# MacroPad.net
KiCad netlist of a schematic drawn in EAGLE
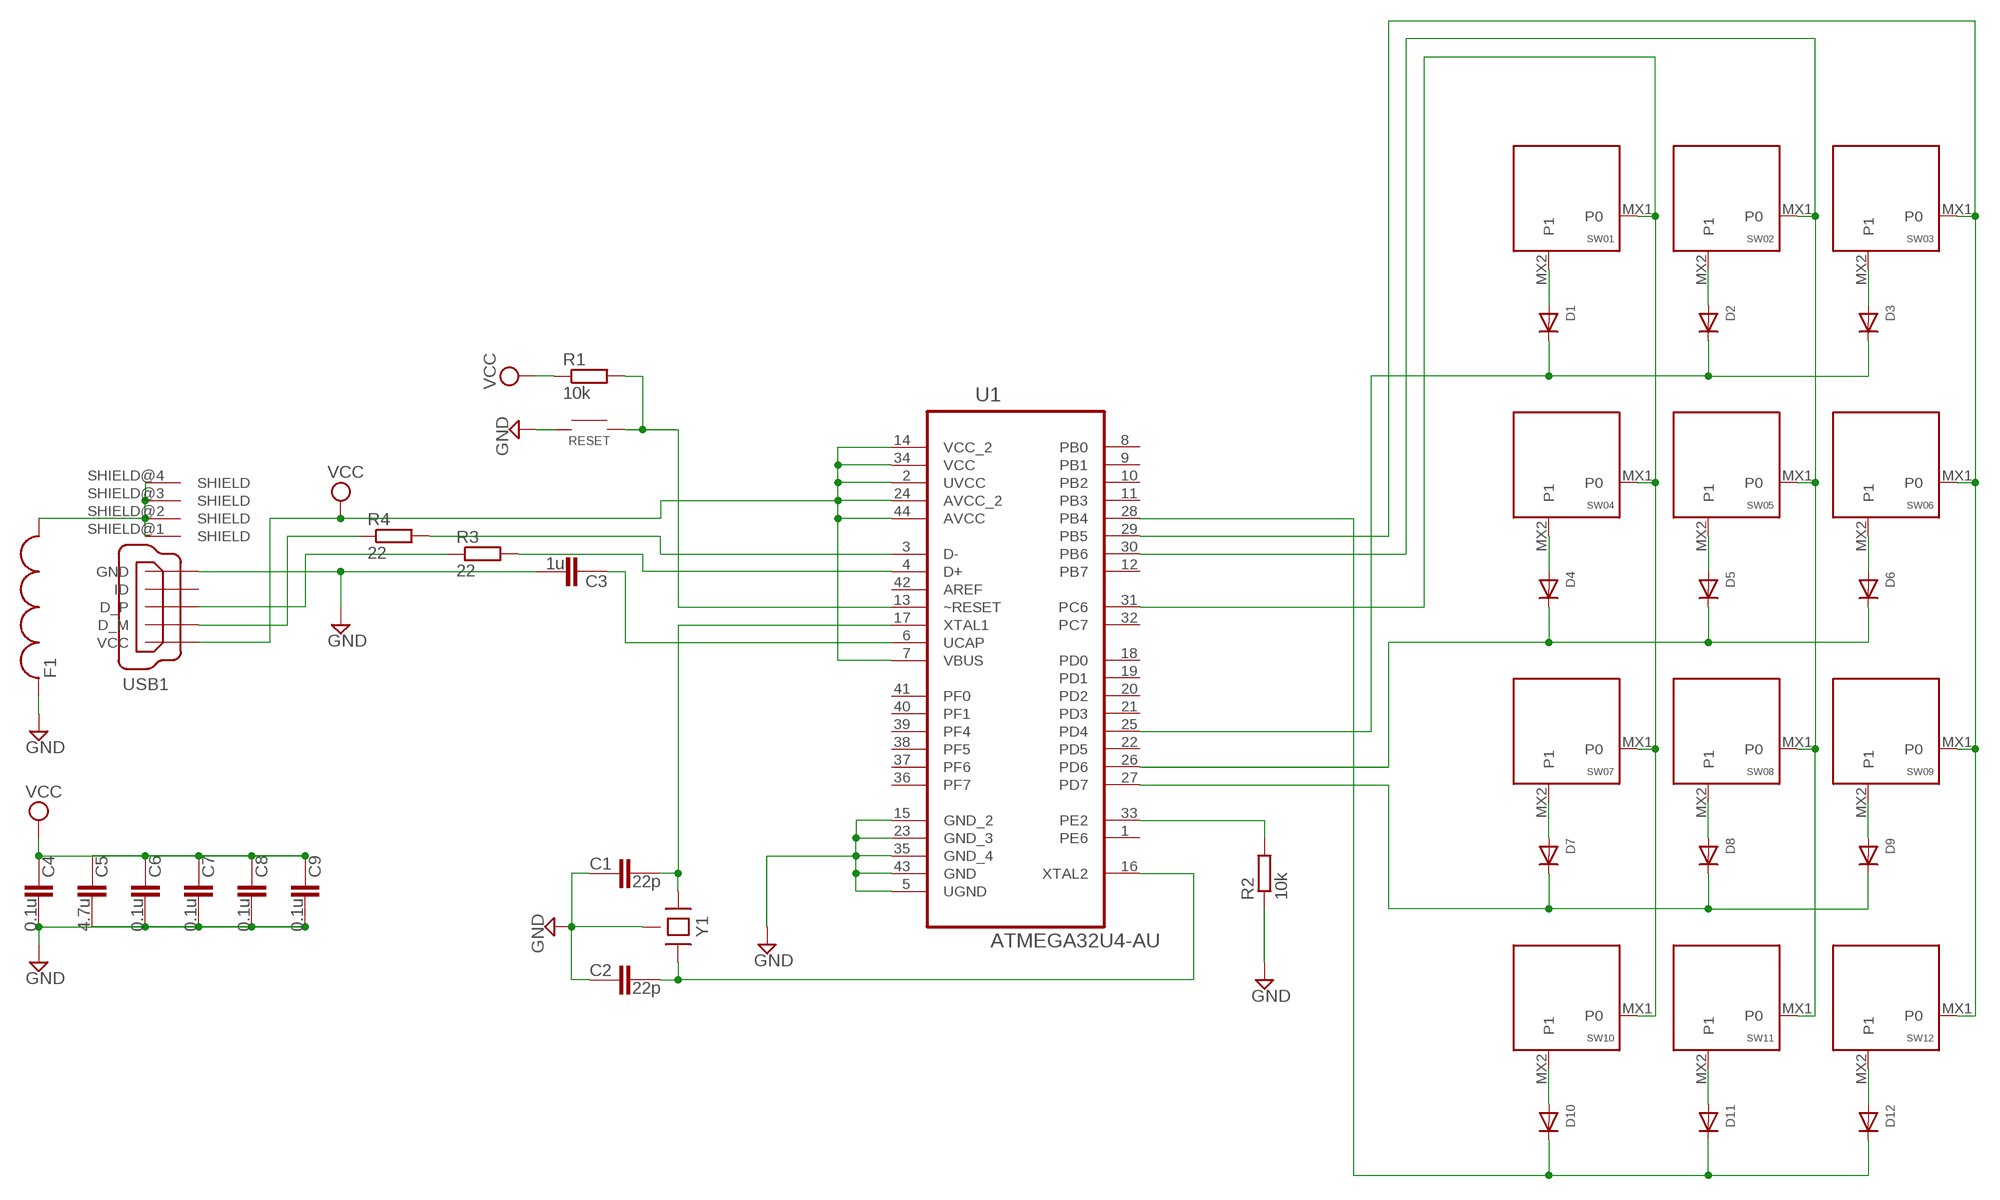
[diagram p0: schematic, sheet 1]

(export (version "E")
  (design (tool "Eeschema 10.0.6"))
  (components
    (comp (ref "C1")
      (value "22p")
      (footprint "eagle-import:C0603")
      (fields (field (name "MPN") "04025A220JAT2A"))
      (libsource (lib "eagle-import") (part "CAPACITOR-0603"))
    )
    (comp (ref "C2")
      (value "22p")
      (footprint "eagle-import:C0603")
      (fields (field (name "MPN") "04025A220JAT2A"))
      (libsource (lib "eagle-import") (part "CAPACITOR-0603"))
    )
    (comp (ref "C3")
      (value "1u")
      (footprint "eagle-import:C0603")
      (libsource (lib "eagle-import") (part "CAPACITOR-0603"))
    )
    (comp (ref "C4")
      (value "0.1u")
      (footprint "eagle-import:C0603")
      (libsource (lib "eagle-import") (part "CAPACITOR-0603"))
    )
    (comp (ref "C5")
      (value "4.7u")
      (footprint "eagle-import:C0603")
      (libsource (lib "eagle-import") (part "CAPACITOR-0603"))
    )
    (comp (ref "C6")
      (value "0.1u")
      (footprint "eagle-import:C0603")
      (libsource (lib "eagle-import") (part "CAPACITOR-0603"))
    )
    (comp (ref "C7")
      (value "0.1u")
      (footprint "eagle-import:C0603")
      (libsource (lib "eagle-import") (part "CAPACITOR-0603"))
    )
    (comp (ref "C8")
      (value "0.1u")
      (footprint "eagle-import:C0603")
      (libsource (lib "eagle-import") (part "CAPACITOR-0603"))
    )
    (comp (ref "C9")
      (value "0.1u")
      (footprint "eagle-import:C0603")
      (libsource (lib "eagle-import") (part "CAPACITOR-0603"))
    )
    (comp (ref "D1")
      (value "DIODEDO-1N4148")
      (footprint "eagle-import:DO-1N4148")
      (libsource (lib "eagle-import") (part "DIODEDO-1N4148"))
    )
    (comp (ref "D2")
      (value "DIODEDO-1N4148")
      (footprint "eagle-import:DO-1N4148")
      (libsource (lib "eagle-import") (part "DIODEDO-1N4148"))
    )
    (comp (ref "D3")
      (value "DIODEDO-1N4148")
      (footprint "eagle-import:DO-1N4148")
      (libsource (lib "eagle-import") (part "DIODEDO-1N4148"))
    )
    (comp (ref "D4")
      (value "DIODEDO-1N4148")
      (footprint "eagle-import:DO-1N4148")
      (libsource (lib "eagle-import") (part "DIODEDO-1N4148"))
    )
    (comp (ref "D5")
      (value "DIODEDO-1N4148")
      (footprint "eagle-import:DO-1N4148")
      (libsource (lib "eagle-import") (part "DIODEDO-1N4148"))
    )
    (comp (ref "D6")
      (value "DIODEDO-1N4148")
      (footprint "eagle-import:DO-1N4148")
      (libsource (lib "eagle-import") (part "DIODEDO-1N4148"))
    )
    (comp (ref "D7")
      (value "DIODEDO-1N4148")
      (footprint "eagle-import:DO-1N4148")
      (libsource (lib "eagle-import") (part "DIODEDO-1N4148"))
    )
    (comp (ref "D8")
      (value "DIODEDO-1N4148")
      (footprint "eagle-import:DO-1N4148")
      (libsource (lib "eagle-import") (part "DIODEDO-1N4148"))
    )
    (comp (ref "D9")
      (value "DIODEDO-1N4148")
      (footprint "eagle-import:DO-1N4148")
      (libsource (lib "eagle-import") (part "DIODEDO-1N4148"))
    )
    (comp (ref "D10")
      (value "DIODEDO-1N4148")
      (footprint "eagle-import:DO-1N4148")
      (libsource (lib "eagle-import") (part "DIODEDO-1N4148"))
    )
    (comp (ref "D11")
      (value "DIODEDO-1N4148")
      (footprint "eagle-import:DO-1N4148")
      (libsource (lib "eagle-import") (part "DIODEDO-1N4148"))
    )
    (comp (ref "D12")
      (value "DIODEDO-1N4148")
      (footprint "eagle-import:DO-1N4148")
      (libsource (lib "eagle-import") (part "DIODEDO-1N4148"))
    )
    (comp (ref "F1")
      (value "FERRITE-0805")
      (footprint "eagle-import:F0805")
      (libsource (lib "eagle-import") (part "FERRITE-0805"))
    )
    (comp (ref "R1")
      (value "10k")
      (footprint "eagle-import:R0603")
      (libsource (lib "eagle-import") (part "RESISTOR-0603"))
    )
    (comp (ref "R2")
      (value "10k")
      (footprint "eagle-import:R0603")
      (libsource (lib "eagle-import") (part "RESISTOR-0603"))
    )
    (comp (ref "R3")
      (value "22")
      (footprint "eagle-import:R0603")
      (libsource (lib "eagle-import") (part "RESISTOR-0603"))
    )
    (comp (ref "R4")
      (value "22")
      (footprint "eagle-import:R0603")
      (libsource (lib "eagle-import") (part "RESISTOR-0603"))
    )
    (comp (ref "RESET")
      (value "SWITCH-SMD-EVQP-P2602W")
      (footprint "eagle-import:SWITCH-SMD-EVQP-P2602W")
      (libsource (lib "eagle-import") (part "SWITCH-SMD-EVQP-P2602W"))
    )
    (comp (ref "SW01")
      (value "KEYSWITCH-PLAIN-MX-1U")
      (footprint "eagle-import:MX-1U")
      (libsource (lib "eagle-import") (part "KEYSWITCH-PLAIN-MX-1U"))
    )
    (comp (ref "SW02")
      (value "KEYSWITCH-PLAIN-MX-1U")
      (footprint "eagle-import:MX-1U")
      (libsource (lib "eagle-import") (part "KEYSWITCH-PLAIN-MX-1U"))
    )
    (comp (ref "SW03")
      (value "KEYSWITCH-PLAIN-MX-1U")
      (footprint "eagle-import:MX-1U")
      (libsource (lib "eagle-import") (part "KEYSWITCH-PLAIN-MX-1U"))
    )
    (comp (ref "SW04")
      (value "KEYSWITCH-PLAIN-MX-1U")
      (footprint "eagle-import:MX-1U")
      (libsource (lib "eagle-import") (part "KEYSWITCH-PLAIN-MX-1U"))
    )
    (comp (ref "SW05")
      (value "KEYSWITCH-PLAIN-MX-1U")
      (footprint "eagle-import:MX-1U")
      (libsource (lib "eagle-import") (part "KEYSWITCH-PLAIN-MX-1U"))
    )
    (comp (ref "SW06")
      (value "KEYSWITCH-PLAIN-MX-1U")
      (footprint "eagle-import:MX-1U")
      (libsource (lib "eagle-import") (part "KEYSWITCH-PLAIN-MX-1U"))
    )
    (comp (ref "SW07")
      (value "KEYSWITCH-PLAIN-MX-1U")
      (footprint "eagle-import:MX-1U")
      (libsource (lib "eagle-import") (part "KEYSWITCH-PLAIN-MX-1U"))
    )
    (comp (ref "SW08")
      (value "KEYSWITCH-PLAIN-MX-1U")
      (footprint "eagle-import:MX-1U")
      (libsource (lib "eagle-import") (part "KEYSWITCH-PLAIN-MX-1U"))
    )
    (comp (ref "SW09")
      (value "KEYSWITCH-PLAIN-MX-1U")
      (footprint "eagle-import:MX-1U")
      (libsource (lib "eagle-import") (part "KEYSWITCH-PLAIN-MX-1U"))
    )
    (comp (ref "SW10")
      (value "KEYSWITCH-PLAIN-MX-1U")
      (footprint "eagle-import:MX-1U")
      (libsource (lib "eagle-import") (part "KEYSWITCH-PLAIN-MX-1U"))
    )
    (comp (ref "SW11")
      (value "KEYSWITCH-PLAIN-MX-1U")
      (footprint "eagle-import:MX-1U")
      (libsource (lib "eagle-import") (part "KEYSWITCH-PLAIN-MX-1U"))
    )
    (comp (ref "SW12")
      (value "KEYSWITCH-PLAIN-MX-1U")
      (footprint "eagle-import:MX-1U")
      (libsource (lib "eagle-import") (part "KEYSWITCH-PLAIN-MX-1U"))
    )
    (comp (ref "U1")
      (value "ATMEGA32U4-AU")
      (footprint "eagle-import:QFP80P1200X1200X120-44N")
      (fields (field (name "MF") "Microchip"))
      (libsource (lib "eagle-import") (part "ATMEGA32U4-AU"))
    )
    (comp (ref "USB1")
      (value "USB_CONN-MINI-FEMALE")
      (footprint "eagle-import:UX60-MB-5S8")
      (libsource (lib "eagle-import") (part "USB_CONN-MINI-FEMALE"))
    )
    (comp (ref "Y1")
      (value "CRYSTAL-4PIN-3.2X5")
      (footprint "eagle-import:CRYSTAL-3.2X5")
      (libsource (lib "eagle-import") (part "CRYSTAL-4PIN-3.2X5"))
    )
  )
  (nets
    (net (code "1") (name "GND") (class "Default")
      (node (ref "C1") (pin "1") (pinfunction "1_1") (pintype "passive"))
      (node (ref "C2") (pin "1") (pinfunction "1_1") (pintype "passive"))
      (node (ref "C3") (pin "2") (pinfunction "2_2") (pintype "passive"))
      (node (ref "C4") (pin "2") (pinfunction "2_2") (pintype "passive"))
      (node (ref "C5") (pin "2") (pinfunction "2_2") (pintype "passive"))
      (node (ref "C6") (pin "2") (pinfunction "2_2") (pintype "passive"))
      (node (ref "C7") (pin "2") (pinfunction "2_2") (pintype "passive"))
      (node (ref "C8") (pin "2") (pinfunction "2_2") (pintype "passive"))
      (node (ref "C9") (pin "2") (pinfunction "2_2") (pintype "passive"))
      (node (ref "F1") (pin "1") (pinfunction "P$1_1") (pintype "bidirectional"))
      (node (ref "R2") (pin "1") (pinfunction "1_1") (pintype "passive"))
      (node (ref "RESET") (pin "1A") (pinfunction "1_1A") (pintype "passive"))
      (node (ref "RESET") (pin "1B") (pinfunction "1_1B") (pintype "passive"))
      (node (ref "U1") (pin "15") (pinfunction "GND_2_15") (pintype "passive"))
      (node (ref "U1") (pin "23") (pinfunction "GND_3_23") (pintype "passive"))
      (node (ref "U1") (pin "35") (pinfunction "GND_4_35") (pintype "passive"))
      (node (ref "U1") (pin "43") (pinfunction "GND_43") (pintype "passive"))
      (node (ref "U1") (pin "5") (pinfunction "UGND_5") (pintype "passive"))
      (node (ref "USB1") (pin "GND") (pinfunction "GND_GND") (pintype "input"))
      (node (ref "Y1") (pin "2") (pinfunction "GND_2") (pintype "bidirectional"))
      (node (ref "Y1") (pin "4") (pinfunction "GND_4") (pintype "bidirectional"))
    )
    (net (code "2") (name "Net-(F1-P$2)") (class "Default")
      (node (ref "F1") (pin "2") (pinfunction "P$2_2") (pintype "bidirectional"))
      (node (ref "USB1") (pin "SHIELD@1") (pinfunction "SHIELD_SHIELD@1") (pintype "bidirectional"))
      (node (ref "USB1") (pin "SHIELD@2") (pinfunction "SHIELD_SHIELD@2") (pintype "bidirectional"))
      (node (ref "USB1") (pin "SHIELD@3") (pinfunction "SHIELD_SHIELD@3") (pintype "bidirectional"))
      (node (ref "USB1") (pin "SHIELD@4") (pinfunction "SHIELD_SHIELD@4") (pintype "bidirectional"))
    )
    (net (code "3") (name "Net-(SW01-P0)") (class "Default")
      (node (ref "SW01") (pin "MX1") (pinfunction "P0_MX1") (pintype "bidirectional"))
      (node (ref "SW04") (pin "MX1") (pinfunction "P0_MX1") (pintype "bidirectional"))
      (node (ref "SW07") (pin "MX1") (pinfunction "P0_MX1") (pintype "bidirectional"))
      (node (ref "SW10") (pin "MX1") (pinfunction "P0_MX1") (pintype "bidirectional"))
      (node (ref "U1") (pin "31") (pinfunction "PC6_31") (pintype "bidirectional"))
    )
    (net (code "4") (name "Net-(SW01-P1)") (class "Default")
      (node (ref "D1") (pin "A") (pinfunction "A_A") (pintype "passive"))
      (node (ref "SW01") (pin "MX2") (pinfunction "P1_MX2") (pintype "bidirectional"))
    )
    (net (code "5") (name "Net-(SW02-P0)") (class "Default")
      (node (ref "SW02") (pin "MX1") (pinfunction "P0_MX1") (pintype "bidirectional"))
      (node (ref "SW05") (pin "MX1") (pinfunction "P0_MX1") (pintype "bidirectional"))
      (node (ref "SW08") (pin "MX1") (pinfunction "P0_MX1") (pintype "bidirectional"))
      (node (ref "SW11") (pin "MX1") (pinfunction "P0_MX1") (pintype "bidirectional"))
      (node (ref "U1") (pin "30") (pinfunction "PB6_30") (pintype "bidirectional"))
    )
    (net (code "6") (name "Net-(SW02-P1)") (class "Default")
      (node (ref "D2") (pin "A") (pinfunction "A_A") (pintype "passive"))
      (node (ref "SW02") (pin "MX2") (pinfunction "P1_MX2") (pintype "bidirectional"))
    )
    (net (code "7") (name "Net-(SW03-P0)") (class "Default")
      (node (ref "SW03") (pin "MX1") (pinfunction "P0_MX1") (pintype "bidirectional"))
      (node (ref "SW06") (pin "MX1") (pinfunction "P0_MX1") (pintype "bidirectional"))
      (node (ref "SW09") (pin "MX1") (pinfunction "P0_MX1") (pintype "bidirectional"))
      (node (ref "SW12") (pin "MX1") (pinfunction "P0_MX1") (pintype "bidirectional"))
      (node (ref "U1") (pin "29") (pinfunction "PB5_29") (pintype "bidirectional"))
    )
    (net (code "8") (name "Net-(SW03-P1)") (class "Default")
      (node (ref "D3") (pin "A") (pinfunction "A_A") (pintype "passive"))
      (node (ref "SW03") (pin "MX2") (pinfunction "P1_MX2") (pintype "bidirectional"))
    )
    (net (code "9") (name "Net-(SW04-P1)") (class "Default")
      (node (ref "D4") (pin "A") (pinfunction "A_A") (pintype "passive"))
      (node (ref "SW04") (pin "MX2") (pinfunction "P1_MX2") (pintype "bidirectional"))
    )
    (net (code "10") (name "Net-(SW05-P1)") (class "Default")
      (node (ref "D5") (pin "A") (pinfunction "A_A") (pintype "passive"))
      (node (ref "SW05") (pin "MX2") (pinfunction "P1_MX2") (pintype "bidirectional"))
    )
    (net (code "11") (name "Net-(SW06-P1)") (class "Default")
      (node (ref "D6") (pin "A") (pinfunction "A_A") (pintype "passive"))
      (node (ref "SW06") (pin "MX2") (pinfunction "P1_MX2") (pintype "bidirectional"))
    )
    (net (code "12") (name "Net-(SW07-P1)") (class "Default")
      (node (ref "D7") (pin "A") (pinfunction "A_A") (pintype "passive"))
      (node (ref "SW07") (pin "MX2") (pinfunction "P1_MX2") (pintype "bidirectional"))
    )
    (net (code "13") (name "Net-(SW08-P1)") (class "Default")
      (node (ref "D8") (pin "A") (pinfunction "A_A") (pintype "passive"))
      (node (ref "SW08") (pin "MX2") (pinfunction "P1_MX2") (pintype "bidirectional"))
    )
    (net (code "14") (name "Net-(SW09-P1)") (class "Default")
      (node (ref "D9") (pin "A") (pinfunction "A_A") (pintype "passive"))
      (node (ref "SW09") (pin "MX2") (pinfunction "P1_MX2") (pintype "bidirectional"))
    )
    (net (code "15") (name "Net-(SW10-P1)") (class "Default")
      (node (ref "D10") (pin "A") (pinfunction "A_A") (pintype "passive"))
      (node (ref "SW10") (pin "MX2") (pinfunction "P1_MX2") (pintype "bidirectional"))
    )
    (net (code "16") (name "Net-(SW11-P1)") (class "Default")
      (node (ref "D11") (pin "A") (pinfunction "A_A") (pintype "passive"))
      (node (ref "SW11") (pin "MX2") (pinfunction "P1_MX2") (pintype "bidirectional"))
    )
    (net (code "17") (name "Net-(SW12-P1)") (class "Default")
      (node (ref "D12") (pin "A") (pinfunction "A_A") (pintype "passive"))
      (node (ref "SW12") (pin "MX2") (pinfunction "P1_MX2") (pintype "bidirectional"))
    )
    (net (code "18") (name "Net-(U1-D+)") (class "Default")
      (node (ref "R3") (pin "2") (pinfunction "2_2") (pintype "passive"))
      (node (ref "U1") (pin "4") (pinfunction "D+_4") (pintype "passive"))
    )
    (net (code "19") (name "Net-(U1-D-)") (class "Default")
      (node (ref "R4") (pin "2") (pinfunction "2_2") (pintype "passive"))
      (node (ref "U1") (pin "3") (pinfunction "D-_3") (pintype "passive"))
    )
    (net (code "20") (name "Net-(U1-PB4)") (class "Default")
      (node (ref "D10") (pin "C") (pinfunction "C_C") (pintype "passive"))
      (node (ref "D11") (pin "C") (pinfunction "C_C") (pintype "passive"))
      (node (ref "D12") (pin "C") (pinfunction "C_C") (pintype "passive"))
      (node (ref "U1") (pin "28") (pinfunction "PB4_28") (pintype "bidirectional"))
    )
    (net (code "21") (name "Net-(U1-PD4)") (class "Default")
      (node (ref "D1") (pin "C") (pinfunction "C_C") (pintype "passive"))
      (node (ref "D2") (pin "C") (pinfunction "C_C") (pintype "passive"))
      (node (ref "D3") (pin "C") (pinfunction "C_C") (pintype "passive"))
      (node (ref "U1") (pin "25") (pinfunction "PD4_25") (pintype "bidirectional"))
    )
    (net (code "22") (name "Net-(U1-PD6)") (class "Default")
      (node (ref "D4") (pin "C") (pinfunction "C_C") (pintype "passive"))
      (node (ref "D5") (pin "C") (pinfunction "C_C") (pintype "passive"))
      (node (ref "D6") (pin "C") (pinfunction "C_C") (pintype "passive"))
      (node (ref "U1") (pin "26") (pinfunction "PD6_26") (pintype "bidirectional"))
    )
    (net (code "23") (name "Net-(U1-PD7)") (class "Default")
      (node (ref "D7") (pin "C") (pinfunction "C_C") (pintype "passive"))
      (node (ref "D8") (pin "C") (pinfunction "C_C") (pintype "passive"))
      (node (ref "D9") (pin "C") (pinfunction "C_C") (pintype "passive"))
      (node (ref "U1") (pin "27") (pinfunction "PD7_27") (pintype "bidirectional"))
    )
    (net (code "24") (name "Net-(U1-PE2)") (class "Default")
      (node (ref "R2") (pin "2") (pinfunction "2_2") (pintype "passive"))
      (node (ref "U1") (pin "33") (pinfunction "PE2_33") (pintype "bidirectional"))
    )
    (net (code "25") (name "Net-(U1-UCAP)") (class "Default")
      (node (ref "C3") (pin "1") (pinfunction "1_1") (pintype "passive"))
      (node (ref "U1") (pin "6") (pinfunction "UCAP_6") (pintype "power_in"))
    )
    (net (code "26") (name "Net-(U1-XTAL1)") (class "Default")
      (node (ref "C1") (pin "2") (pinfunction "2_2") (pintype "passive"))
      (node (ref "U1") (pin "17") (pinfunction "XTAL1_17") (pintype "input"))
      (node (ref "Y1") (pin "1") (pinfunction "1_1") (pintype "passive"))
    )
    (net (code "27") (name "Net-(U1-XTAL2)") (class "Default")
      (node (ref "C2") (pin "2") (pinfunction "2_2") (pintype "passive"))
      (node (ref "U1") (pin "16") (pinfunction "XTAL2_16") (pintype "output"))
      (node (ref "Y1") (pin "3") (pinfunction "2_3") (pintype "passive"))
    )
    (net (code "28") (name "Net-(U1-~{RESET})") (class "Default")
      (node (ref "R1") (pin "2") (pinfunction "2_2") (pintype "passive"))
      (node (ref "RESET") (pin "2A") (pinfunction "2_2A") (pintype "passive"))
      (node (ref "RESET") (pin "2B") (pinfunction "2_2B") (pintype "passive"))
      (node (ref "U1") (pin "13") (pinfunction "~{RESET}_13") (pintype "input"))
    )
    (net (code "29") (name "Net-(USB1-D_M)") (class "Default")
      (node (ref "R4") (pin "1") (pinfunction "1_1") (pintype "passive"))
      (node (ref "USB1") (pin "D-") (pinfunction "D_M_D-") (pintype "input"))
    )
    (net (code "30") (name "Net-(USB1-D_P)") (class "Default")
      (node (ref "R3") (pin "1") (pinfunction "1_1") (pintype "passive"))
      (node (ref "USB1") (pin "D+") (pinfunction "D_P_D+") (pintype "input"))
    )
    (net (code "31") (name "VCC") (class "Default")
      (node (ref "C4") (pin "1") (pinfunction "1_1") (pintype "passive"))
      (node (ref "C5") (pin "1") (pinfunction "1_1") (pintype "passive"))
      (node (ref "C6") (pin "1") (pinfunction "1_1") (pintype "passive"))
      (node (ref "C7") (pin "1") (pinfunction "1_1") (pintype "passive"))
      (node (ref "C8") (pin "1") (pinfunction "1_1") (pintype "passive"))
      (node (ref "C9") (pin "1") (pinfunction "1_1") (pintype "passive"))
      (node (ref "R1") (pin "1") (pinfunction "1_1") (pintype "passive"))
      (node (ref "U1") (pin "14") (pinfunction "VCC_2_14") (pintype "power_in"))
      (node (ref "U1") (pin "2") (pinfunction "UVCC_2") (pintype "power_in"))
      (node (ref "U1") (pin "24") (pinfunction "AVCC_2_24") (pintype "power_in"))
      (node (ref "U1") (pin "34") (pinfunction "VCC_34") (pintype "power_in"))
      (node (ref "U1") (pin "44") (pinfunction "AVCC_44") (pintype "power_in"))
      (node (ref "U1") (pin "7") (pinfunction "VBUS_7") (pintype "input"))
      (node (ref "USB1") (pin "VCC") (pinfunction "VCC_VCC") (pintype "input"))
    )
    (net (code "32") (name "unconnected-(U1-AREF-Pad42)") (class "Default")
      (node (ref "U1") (pin "42") (pinfunction "AREF_42") (pintype "input"))
    )
    (net (code "33") (name "unconnected-(U1-PB0-Pad8)") (class "Default")
      (node (ref "U1") (pin "8") (pinfunction "PB0_8") (pintype "bidirectional"))
    )
    (net (code "34") (name "unconnected-(U1-PB1-Pad9)") (class "Default")
      (node (ref "U1") (pin "9") (pinfunction "PB1_9") (pintype "bidirectional"))
    )
    (net (code "35") (name "unconnected-(U1-PB2-Pad10)") (class "Default")
      (node (ref "U1") (pin "10") (pinfunction "PB2_10") (pintype "bidirectional"))
    )
    (net (code "36") (name "unconnected-(U1-PB3-Pad11)") (class "Default")
      (node (ref "U1") (pin "11") (pinfunction "PB3_11") (pintype "bidirectional"))
    )
    (net (code "37") (name "unconnected-(U1-PB7-Pad12)") (class "Default")
      (node (ref "U1") (pin "12") (pinfunction "PB7_12") (pintype "bidirectional"))
    )
    (net (code "38") (name "unconnected-(U1-PC7-Pad32)") (class "Default")
      (node (ref "U1") (pin "32") (pinfunction "PC7_32") (pintype "bidirectional"))
    )
    (net (code "39") (name "unconnected-(U1-PD0-Pad18)") (class "Default")
      (node (ref "U1") (pin "18") (pinfunction "PD0_18") (pintype "bidirectional"))
    )
    (net (code "40") (name "unconnected-(U1-PD1-Pad19)") (class "Default")
      (node (ref "U1") (pin "19") (pinfunction "PD1_19") (pintype "bidirectional"))
    )
    (net (code "41") (name "unconnected-(U1-PD2-Pad20)") (class "Default")
      (node (ref "U1") (pin "20") (pinfunction "PD2_20") (pintype "bidirectional"))
    )
    (net (code "42") (name "unconnected-(U1-PD3-Pad21)") (class "Default")
      (node (ref "U1") (pin "21") (pinfunction "PD3_21") (pintype "bidirectional"))
    )
    (net (code "43") (name "unconnected-(U1-PD5-Pad22)") (class "Default")
      (node (ref "U1") (pin "22") (pinfunction "PD5_22") (pintype "bidirectional"))
    )
    (net (code "44") (name "unconnected-(U1-PE6-Pad1)") (class "Default")
      (node (ref "U1") (pin "1") (pinfunction "PE6_1") (pintype "bidirectional"))
    )
    (net (code "45") (name "unconnected-(U1-PF0-Pad41)") (class "Default")
      (node (ref "U1") (pin "41") (pinfunction "PF0_41") (pintype "bidirectional"))
    )
    (net (code "46") (name "unconnected-(U1-PF1-Pad40)") (class "Default")
      (node (ref "U1") (pin "40") (pinfunction "PF1_40") (pintype "bidirectional"))
    )
    (net (code "47") (name "unconnected-(U1-PF4-Pad39)") (class "Default")
      (node (ref "U1") (pin "39") (pinfunction "PF4_39") (pintype "bidirectional"))
    )
    (net (code "48") (name "unconnected-(U1-PF5-Pad38)") (class "Default")
      (node (ref "U1") (pin "38") (pinfunction "PF5_38") (pintype "bidirectional"))
    )
    (net (code "49") (name "unconnected-(U1-PF6-Pad37)") (class "Default")
      (node (ref "U1") (pin "37") (pinfunction "PF6_37") (pintype "bidirectional"))
    )
    (net (code "50") (name "unconnected-(U1-PF7-Pad36)") (class "Default")
      (node (ref "U1") (pin "36") (pinfunction "PF7_36") (pintype "bidirectional"))
    )
    (net (code "51") (name "unconnected-(USB1-PadID)") (class "Default")
      (node (ref "USB1") (pin "ID") (pinfunction "ID_ID") (pintype "input"))
    )
  )
)
